# pcb.net
KiCad netlist of a schematic drawn in EasyEDA Pro
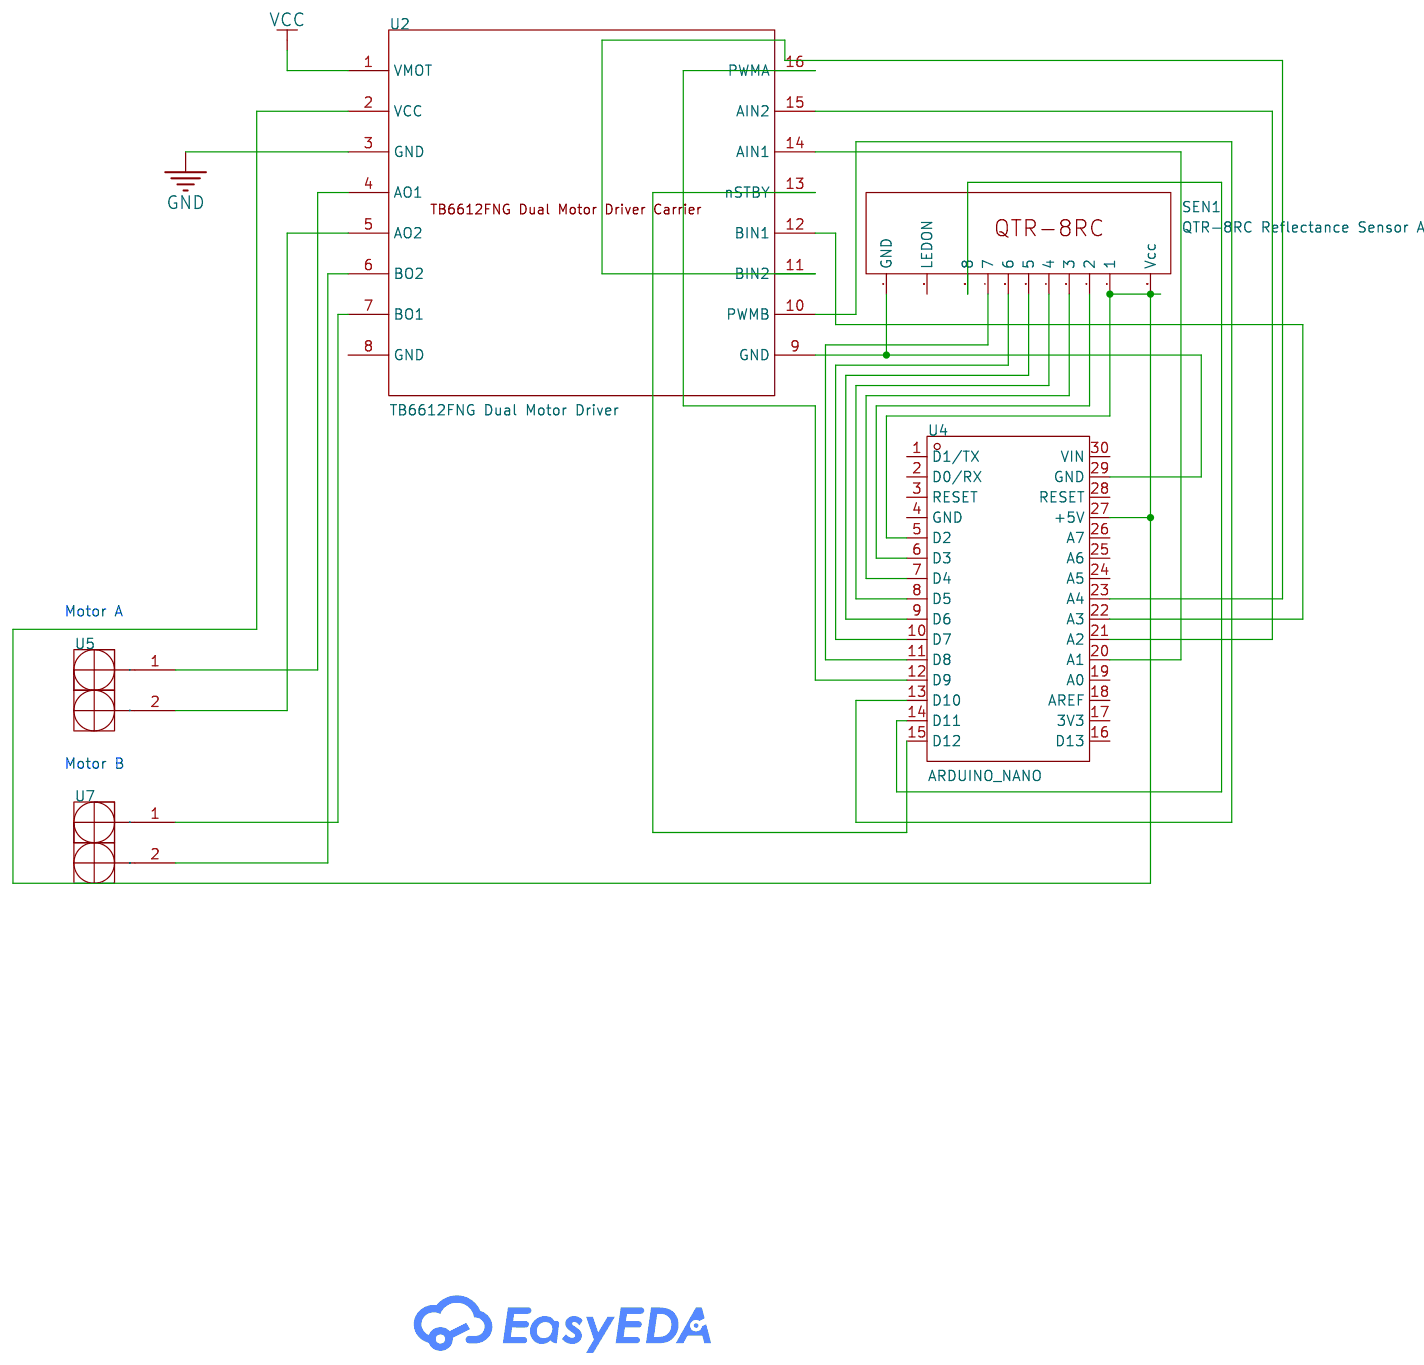
[diagram p0: schematic sheet]

(export (version "E")
  (design (tool "Eeschema 10.0.6"))
  (components
    (comp (ref "SEN1")
      (value "QTR-8RC Reflectance Sensor Array")
      (footprint "easyedapro:QTR-8X")
      (fields (field (name "Manufacturer") "Pololu"))
      (libsource (lib "easyedapro") (part "QTR-8RC Reflectance Sensor Array"))
    )
    (comp (ref "U2")
      (value "TB6612FNG Dual Motor Driver")
      (footprint "easyedapro:TB6612FNG")
      (libsource (lib "easyedapro") (part "TB6612FNG Dual Motor Driver"))
    )
    (comp (ref "U4")
      (value "ARDUINO_NANO")
      (footprint "easyedapro:COMM-TH_ARDUINO_NANO")
      (libsource (lib "easyedapro") (part "ARDUINO_NANO"))
    )
    (comp (ref "U5")
      (value "~")
      (footprint "easyedapro:2PIN SCREW TERMINAL")
      (libsource (lib "easyedapro") (part "2PIN SCREW TERMINAL"))
    )
    (comp (ref "U7")
      (value "~")
      (footprint "easyedapro:2PIN SCREW TERMINAL")
      (libsource (lib "easyedapro") (part "2PIN SCREW TERMINAL"))
    )
  )
  (nets
    (net (code "1") (name "GND") (class "Default")
      (node (ref "U2") (pin "3") (pinfunction "GND_3") (pintype "unspecified"))
    )
    (net (code "2") (name "Net-(SEN1-GND)") (class "Default")
      (node (ref "SEN1") (pin "11") (pinfunction "GND_11") (pintype "unspecified"))
      (node (ref "U2") (pin "9") (pinfunction "GND_9") (pintype "unspecified"))
      (node (ref "U4") (pin "29") (pinfunction "GND_29") (pintype "unspecified"))
    )
    (net (code "3") (name "Net-(SEN1-Vcc)") (class "Default")
      (node (ref "SEN1") (pin "1") (pinfunction "1_1") (pintype "unspecified"))
      (node (ref "SEN1") (pin "10") (pinfunction "Vcc_10") (pintype "unspecified"))
      (node (ref "U2") (pin "2") (pinfunction "VCC_2") (pintype "unspecified"))
      (node (ref "U4") (pin "27") (pinfunction "+5V_27") (pintype "unspecified"))
      (node (ref "U4") (pin "5") (pinfunction "D2_5") (pintype "unspecified"))
    )
    (net (code "4") (name "Net-(U2-AIN1)") (class "Default")
      (node (ref "U2") (pin "14") (pinfunction "AIN1_14") (pintype "unspecified"))
      (node (ref "U4") (pin "20") (pinfunction "A1_20") (pintype "unspecified"))
    )
    (net (code "5") (name "Net-(U2-AIN2)") (class "Default")
      (node (ref "U2") (pin "15") (pinfunction "AIN2_15") (pintype "unspecified"))
      (node (ref "U4") (pin "21") (pinfunction "A2_21") (pintype "unspecified"))
    )
    (net (code "6") (name "Net-(U2-AO1)") (class "Default")
      (node (ref "U2") (pin "4") (pinfunction "AO1_4") (pintype "unspecified"))
      (node (ref "U5") (pin "1") (pinfunction "1_1") (pintype "input"))
    )
    (net (code "7") (name "Net-(U2-AO2)") (class "Default")
      (node (ref "U2") (pin "5") (pinfunction "AO2_5") (pintype "unspecified"))
      (node (ref "U5") (pin "2") (pinfunction "2_2") (pintype "input"))
    )
    (net (code "8") (name "Net-(U2-BIN1)") (class "Default")
      (node (ref "U2") (pin "12") (pinfunction "BIN1_12") (pintype "unspecified"))
      (node (ref "U4") (pin "22") (pinfunction "A3_22") (pintype "unspecified"))
    )
    (net (code "9") (name "Net-(U2-BIN2)") (class "Default")
      (node (ref "U2") (pin "11") (pinfunction "BIN2_11") (pintype "unspecified"))
      (node (ref "U4") (pin "23") (pinfunction "A4_23") (pintype "unspecified"))
    )
    (net (code "10") (name "Net-(U2-BO1)") (class "Default")
      (node (ref "U2") (pin "7") (pinfunction "BO1_7") (pintype "unspecified"))
      (node (ref "U7") (pin "1") (pinfunction "1_1") (pintype "input"))
    )
    (net (code "11") (name "Net-(U2-BO2)") (class "Default")
      (node (ref "U2") (pin "6") (pinfunction "BO2_6") (pintype "unspecified"))
      (node (ref "U7") (pin "2") (pinfunction "2_2") (pintype "input"))
    )
    (net (code "12") (name "Net-(U2-PWMA)") (class "Default")
      (node (ref "U2") (pin "16") (pinfunction "PWMA_16") (pintype "unspecified"))
      (node (ref "U4") (pin "12") (pinfunction "D9_12") (pintype "unspecified"))
    )
    (net (code "13") (name "Net-(U2-PWMB)") (class "Default")
      (node (ref "U2") (pin "10") (pinfunction "PWMB_10") (pintype "unspecified"))
      (node (ref "U4") (pin "13") (pinfunction "D10_13") (pintype "unspecified"))
    )
    (net (code "14") (name "Net-(U2-nSTBY)") (class "Default")
      (node (ref "U2") (pin "13") (pinfunction "nSTBY_13") (pintype "unspecified"))
      (node (ref "U4") (pin "15") (pinfunction "D12_15") (pintype "unspecified"))
    )
    (net (code "15") (name "Net-(U4-D3)") (class "Default")
      (node (ref "SEN1") (pin "2") (pinfunction "2_2") (pintype "unspecified"))
      (node (ref "U4") (pin "6") (pinfunction "D3_6") (pintype "unspecified"))
    )
    (net (code "16") (name "Net-(U4-D4)") (class "Default")
      (node (ref "SEN1") (pin "3") (pinfunction "3_3") (pintype "unspecified"))
      (node (ref "U4") (pin "7") (pinfunction "D4_7") (pintype "unspecified"))
    )
    (net (code "17") (name "Net-(U4-D5)") (class "Default")
      (node (ref "SEN1") (pin "4") (pinfunction "4_4") (pintype "unspecified"))
      (node (ref "U4") (pin "8") (pinfunction "D5_8") (pintype "unspecified"))
    )
    (net (code "18") (name "Net-(U4-D6)") (class "Default")
      (node (ref "SEN1") (pin "5") (pinfunction "5_5") (pintype "unspecified"))
      (node (ref "U4") (pin "9") (pinfunction "D6_9") (pintype "unspecified"))
    )
    (net (code "19") (name "Net-(U4-D7)") (class "Default")
      (node (ref "SEN1") (pin "6") (pinfunction "6_6") (pintype "unspecified"))
      (node (ref "U4") (pin "10") (pinfunction "D7_10") (pintype "unspecified"))
    )
    (net (code "20") (name "Net-(U4-D8)") (class "Default")
      (node (ref "SEN1") (pin "7") (pinfunction "7_7") (pintype "unspecified"))
      (node (ref "U4") (pin "11") (pinfunction "D8_11") (pintype "unspecified"))
    )
    (net (code "21") (name "Net-(U4-D11)") (class "Default")
      (node (ref "SEN1") (pin "8") (pinfunction "8_8") (pintype "unspecified"))
      (node (ref "U4") (pin "14") (pinfunction "D11_14") (pintype "unspecified"))
    )
    (net (code "22") (name "VCC") (class "Default")
      (node (ref "U2") (pin "1") (pinfunction "VMOT_1") (pintype "unspecified"))
    )
    (net (code "23") (name "unconnected-(SEN1-LEDON-Pad9)") (class "Default")
      (node (ref "SEN1") (pin "9") (pinfunction "LEDON_9") (pintype "unspecified"))
    )
    (net (code "24") (name "unconnected-(U2-GND-Pad8)") (class "Default")
      (node (ref "U2") (pin "8") (pinfunction "GND_8") (pintype "unspecified"))
    )
    (net (code "25") (name "unconnected-(U4-3V3-Pad17)") (class "Default")
      (node (ref "U4") (pin "17") (pinfunction "3V3_17") (pintype "unspecified"))
    )
    (net (code "26") (name "unconnected-(U4-A0-Pad19)") (class "Default")
      (node (ref "U4") (pin "19") (pinfunction "A0_19") (pintype "unspecified"))
    )
    (net (code "27") (name "unconnected-(U4-A5-Pad24)") (class "Default")
      (node (ref "U4") (pin "24") (pinfunction "A5_24") (pintype "unspecified"))
    )
    (net (code "28") (name "unconnected-(U4-A6-Pad25)") (class "Default")
      (node (ref "U4") (pin "25") (pinfunction "A6_25") (pintype "unspecified"))
    )
    (net (code "29") (name "unconnected-(U4-A7-Pad26)") (class "Default")
      (node (ref "U4") (pin "26") (pinfunction "A7_26") (pintype "unspecified"))
    )
    (net (code "30") (name "unconnected-(U4-AREF-Pad18)") (class "Default")
      (node (ref "U4") (pin "18") (pinfunction "AREF_18") (pintype "unspecified"))
    )
    (net (code "31") (name "unconnected-(U4-D0{slash}RX-Pad2)") (class "Default")
      (node (ref "U4") (pin "2") (pinfunction "D0/RX_2") (pintype "unspecified"))
    )
    (net (code "32") (name "unconnected-(U4-D1{slash}TX-Pad1)") (class "Default")
      (node (ref "U4") (pin "1") (pinfunction "D1/TX_1") (pintype "unspecified"))
    )
    (net (code "33") (name "unconnected-(U4-D13-Pad16)") (class "Default")
      (node (ref "U4") (pin "16") (pinfunction "D13_16") (pintype "unspecified"))
    )
    (net (code "34") (name "unconnected-(U4-GND-Pad4)") (class "Default")
      (node (ref "U4") (pin "4") (pinfunction "GND_4") (pintype "unspecified"))
    )
    (net (code "35") (name "unconnected-(U4-RESET-Pad3)") (class "Default")
      (node (ref "U4") (pin "3") (pinfunction "RESET_3") (pintype "unspecified"))
    )
    (net (code "36") (name "unconnected-(U4-RESET-Pad28)") (class "Default")
      (node (ref "U4") (pin "28") (pinfunction "RESET_28") (pintype "unspecified"))
    )
    (net (code "37") (name "unconnected-(U4-VIN-Pad30)") (class "Default")
      (node (ref "U4") (pin "30") (pinfunction "VIN_30") (pintype "unspecified"))
    )
  )
)
